# mcu.net
KiCad netlist of a schematic drawn in Altium Designer
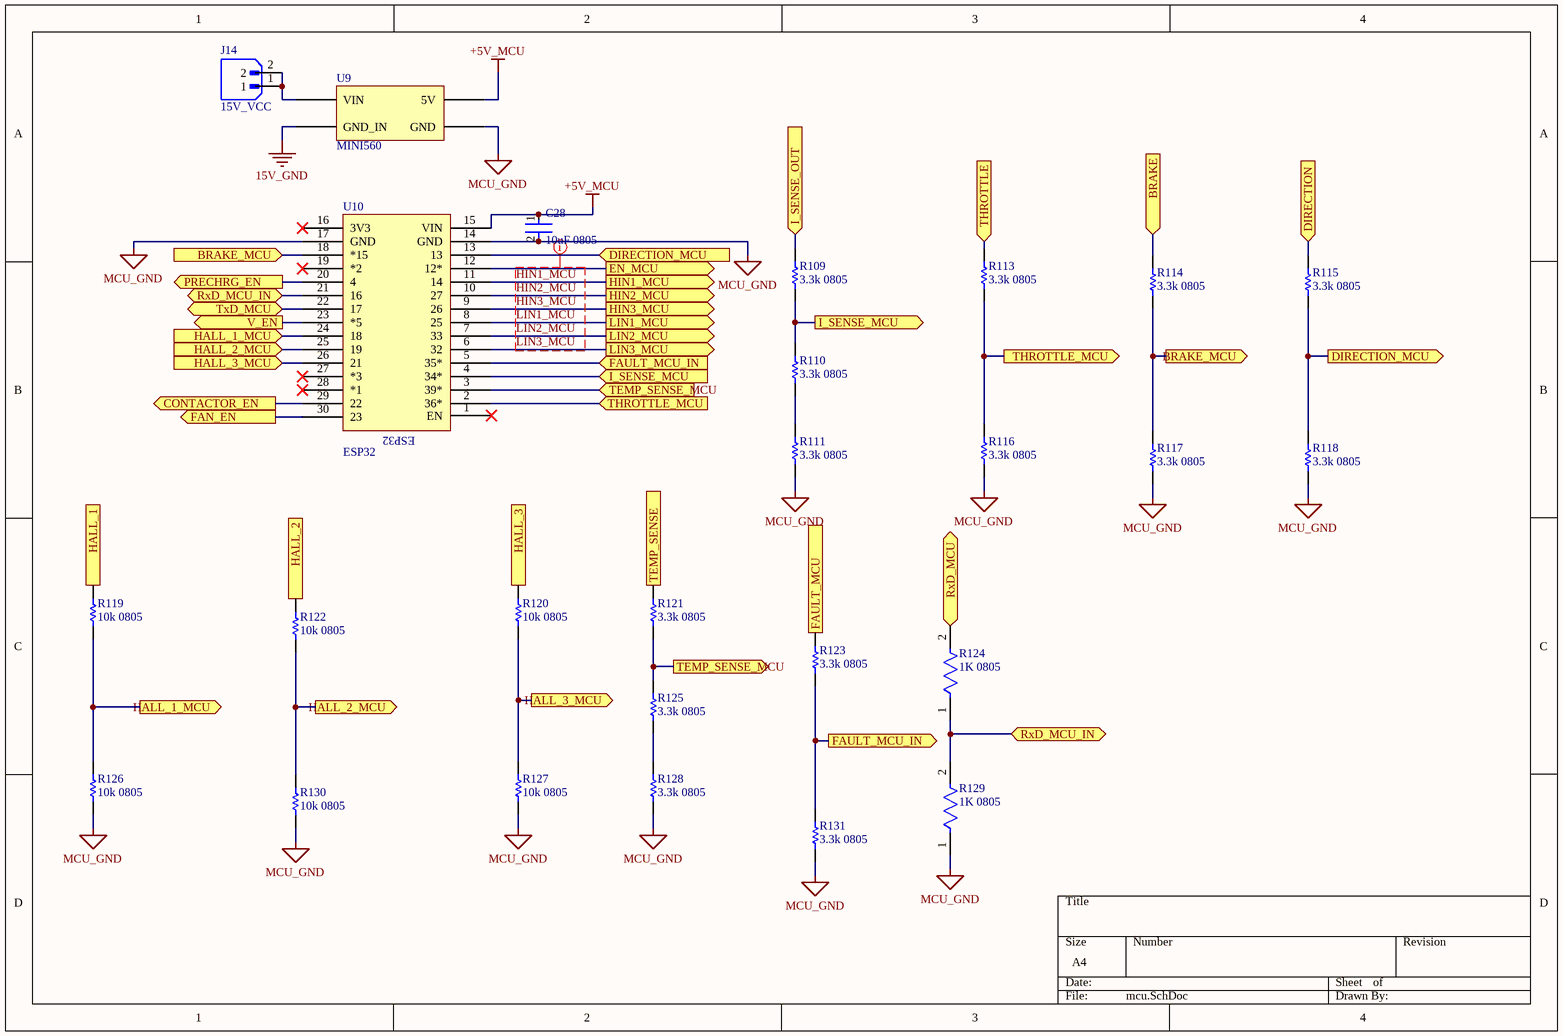
[diagram p0: mcu.SchDoc]

(export (version "E")
  (design (tool "Eeschema 10.0.6"))
  (components
    (comp (ref "C28")
      (value "10uF 0805")
      (footprint "R0805")
      (description "10uF/1000nF 50V Capacitor ±10% Tolerance CC0805KKX5R9BB106 – 0805 Package")
      (libsource (lib "1kW_BLDC_Controller") (part "10uF 0805"))
    )
    (comp (ref "J14")
      (value "15V_VCC")
      (footprint "XH2.5-2p")
      (description "2 Pin JST-XH Male Straight 2515 Connector 2.54mm Pitch")
      (libsource (lib "1kW_BLDC_Controller_1") (part "XH2.5-2p"))
    )
    (comp (ref "R109")
      (value "3.3k 0805")
      (footprint "R0805")
      (description "3.3K Ohm 1/8 Watt Resistor 1% Tolerance RC0805FR-073K3L – 0805 Package")
      (libsource (lib "1kW_BLDC_Controller") (part "R0805"))
    )
    (comp (ref "R110")
      (value "3.3k 0805")
      (footprint "R0805")
      (description "3.3K Ohm 1/8 Watt Resistor 1% Tolerance RC0805FR-073K3L – 0805 Package")
      (libsource (lib "1kW_BLDC_Controller") (part "R0805"))
    )
    (comp (ref "R111")
      (value "3.3k 0805")
      (footprint "R0805")
      (description "3.3K Ohm 1/8 Watt Resistor 1% Tolerance RC0805FR-073K3L – 0805 Package")
      (libsource (lib "1kW_BLDC_Controller") (part "R0805"))
    )
    (comp (ref "R113")
      (value "3.3k 0805")
      (footprint "R0805")
      (description "3.3K Ohm 1/8 Watt Resistor 1% Tolerance RC0805FR-073K3L – 0805 Package")
      (libsource (lib "1kW_BLDC_Controller") (part "R0805"))
    )
    (comp (ref "R114")
      (value "3.3k 0805")
      (footprint "R0805")
      (description "3.3K Ohm 1/8 Watt Resistor 1% Tolerance RC0805FR-073K3L – 0805 Package")
      (libsource (lib "1kW_BLDC_Controller") (part "R0805"))
    )
    (comp (ref "R115")
      (value "3.3k 0805")
      (footprint "R0805")
      (description "3.3K Ohm 1/8 Watt Resistor 1% Tolerance RC0805FR-073K3L – 0805 Package")
      (libsource (lib "1kW_BLDC_Controller") (part "R0805"))
    )
    (comp (ref "R116")
      (value "3.3k 0805")
      (footprint "R0805")
      (description "3.3K Ohm 1/8 Watt Resistor 1% Tolerance RC0805FR-073K3L – 0805 Package")
      (libsource (lib "1kW_BLDC_Controller") (part "R0805"))
    )
    (comp (ref "R117")
      (value "3.3k 0805")
      (footprint "R0805")
      (description "3.3K Ohm 1/8 Watt Resistor 1% Tolerance RC0805FR-073K3L – 0805 Package")
      (libsource (lib "1kW_BLDC_Controller") (part "R0805"))
    )
    (comp (ref "R118")
      (value "3.3k 0805")
      (footprint "R0805")
      (description "3.3K Ohm 1/8 Watt Resistor 1% Tolerance RC0805FR-073K3L – 0805 Package")
      (libsource (lib "1kW_BLDC_Controller") (part "R0805"))
    )
    (comp (ref "R119")
      (value "10k 0805")
      (footprint "R0805")
      (description "10K Ohm 1/8 Watt Resistor 1% Tolerance RC0805FR-0710KL – 0805 Package")
      (libsource (lib "1kW_BLDC_Controller") (part "10k 0805"))
    )
    (comp (ref "R120")
      (value "10k 0805")
      (footprint "R0805")
      (description "10K Ohm 1/8 Watt Resistor 1% Tolerance RC0805FR-0710KL – 0805 Package")
      (libsource (lib "1kW_BLDC_Controller") (part "10k 0805"))
    )
    (comp (ref "R121")
      (value "3.3k 0805")
      (footprint "R0805")
      (description "3.3K Ohm 1/8 Watt Resistor 1% Tolerance RC0805FR-073K3L – 0805 Package")
      (libsource (lib "1kW_BLDC_Controller") (part "R0805"))
    )
    (comp (ref "R122")
      (value "10k 0805")
      (footprint "R0805")
      (description "10K Ohm 1/8 Watt Resistor 1% Tolerance RC0805FR-0710KL – 0805 Package")
      (libsource (lib "1kW_BLDC_Controller") (part "10k 0805"))
    )
    (comp (ref "R123")
      (value "3.3k 0805")
      (footprint "R0805")
      (description "3.3K Ohm 1/8 Watt Resistor 1% Tolerance RC0805FR-073K3L – 0805 Package")
      (libsource (lib "1kW_BLDC_Controller") (part "R0805"))
    )
    (comp (ref "R124")
      (value "1K 0805")
      (footprint "R0805")
      (description "1K Ohm 1/8 Watt Resistor 1% Tolerance 0805S8F1001T5E – 0805 Package")
      (libsource (lib "1kW_BLDC_Controller") (part "1k 0805"))
    )
    (comp (ref "R125")
      (value "3.3k 0805")
      (footprint "R0805")
      (description "3.3K Ohm 1/8 Watt Resistor 1% Tolerance RC0805FR-073K3L – 0805 Package")
      (libsource (lib "1kW_BLDC_Controller") (part "R0805"))
    )
    (comp (ref "R126")
      (value "10k 0805")
      (footprint "R0805")
      (description "10K Ohm 1/8 Watt Resistor 1% Tolerance RC0805FR-0710KL – 0805 Package")
      (libsource (lib "1kW_BLDC_Controller") (part "10k 0805"))
    )
    (comp (ref "R127")
      (value "10k 0805")
      (footprint "R0805")
      (description "10K Ohm 1/8 Watt Resistor 1% Tolerance RC0805FR-0710KL – 0805 Package")
      (libsource (lib "1kW_BLDC_Controller") (part "10k 0805"))
    )
    (comp (ref "R128")
      (value "3.3k 0805")
      (footprint "R0805")
      (description "3.3K Ohm 1/8 Watt Resistor 1% Tolerance RC0805FR-073K3L – 0805 Package")
      (libsource (lib "1kW_BLDC_Controller") (part "R0805"))
    )
    (comp (ref "R129")
      (value "1K 0805")
      (footprint "R0805")
      (description "1K Ohm 1/8 Watt Resistor 1% Tolerance 0805S8F1001T5E – 0805 Package")
      (libsource (lib "1kW_BLDC_Controller") (part "1k 0805"))
    )
    (comp (ref "R130")
      (value "10k 0805")
      (footprint "R0805")
      (description "10K Ohm 1/8 Watt Resistor 1% Tolerance RC0805FR-0710KL – 0805 Package")
      (libsource (lib "1kW_BLDC_Controller") (part "10k 0805"))
    )
    (comp (ref "R131")
      (value "3.3k 0805")
      (footprint "R0805")
      (description "3.3K Ohm 1/8 Watt Resistor 1% Tolerance RC0805FR-073K3L – 0805 Package")
      (libsource (lib "1kW_BLDC_Controller") (part "R0805"))
    )
    (comp (ref "U9")
      (value "MINI560")
      (footprint "MINI560")
      (description "MINI560 5VDC 5A Step-Down Stabilized Module")
      (libsource (lib "1kW_BLDC_Controller") (part "MINI560"))
    )
    (comp (ref "U10")
      (value "ESP32")
      (footprint "esp32")
      (libsource (lib "1kW_BLDC_Controller") (part "ESP32"))
    )
  )
  (nets
    (net (code "1") (name "+5V_MCU") (class "Default")
      (node (ref "C28") (pin "1") (pinfunction "1_1") (pintype "passive"))
      (node (ref "U10") (pin "15") (pinfunction "VIN_15") (pintype "passive"))
      (node (ref "U9") (pin "3") (pinfunction "5V_3") (pintype "power_in"))
    )
    (net (code "2") (name "/BRAKE") (class "Default")
      (node (ref "R114") (pin "2") (pinfunction "2_2") (pintype "passive"))
    )
    (net (code "3") (name "/BRAKE_MCU") (class "Default")
      (node (ref "R114") (pin "1") (pinfunction "1_1") (pintype "passive"))
      (node (ref "R117") (pin "2") (pinfunction "2_2") (pintype "passive"))
      (node (ref "U10") (pin "18") (pinfunction "*15_18") (pintype "passive"))
    )
    (net (code "4") (name "/CONTACTOR_EN") (class "Default")
      (node (ref "U10") (pin "29") (pinfunction "22_29") (pintype "passive"))
    )
    (net (code "5") (name "/DIRECTION") (class "Default")
      (node (ref "R115") (pin "2") (pinfunction "2_2") (pintype "passive"))
    )
    (net (code "6") (name "/DIRECTION_MCU") (class "Default")
      (node (ref "R115") (pin "1") (pinfunction "1_1") (pintype "passive"))
      (node (ref "R118") (pin "2") (pinfunction "2_2") (pintype "passive"))
      (node (ref "U10") (pin "13") (pinfunction "13_13") (pintype "passive"))
    )
    (net (code "7") (name "/EN_MCU") (class "Default")
      (node (ref "U10") (pin "12") (pinfunction "12*_12") (pintype "passive"))
    )
    (net (code "8") (name "/FAN_EN") (class "Default")
      (node (ref "U10") (pin "30") (pinfunction "23_30") (pintype "passive"))
    )
    (net (code "9") (name "/FAULT_MCU") (class "Default")
      (node (ref "R123") (pin "2") (pinfunction "2_2") (pintype "passive"))
    )
    (net (code "10") (name "/FAULT_MCU_IN") (class "Default")
      (node (ref "R123") (pin "1") (pinfunction "1_1") (pintype "passive"))
      (node (ref "R131") (pin "2") (pinfunction "2_2") (pintype "passive"))
      (node (ref "U10") (pin "5") (pinfunction "35*_5") (pintype "passive"))
    )
    (net (code "11") (name "/HALL_1") (class "Default")
      (node (ref "R119") (pin "2") (pinfunction "2_2") (pintype "passive"))
    )
    (net (code "12") (name "/HALL_1_MCU") (class "Default")
      (node (ref "R119") (pin "1") (pinfunction "1_1") (pintype "passive"))
      (node (ref "R126") (pin "2") (pinfunction "2_2") (pintype "passive"))
      (node (ref "U10") (pin "24") (pinfunction "18_24") (pintype "passive"))
    )
    (net (code "13") (name "/HALL_2") (class "Default")
      (node (ref "R122") (pin "2") (pinfunction "2_2") (pintype "passive"))
    )
    (net (code "14") (name "/HALL_2_MCU") (class "Default")
      (node (ref "R122") (pin "1") (pinfunction "1_1") (pintype "passive"))
      (node (ref "R130") (pin "2") (pinfunction "2_2") (pintype "passive"))
      (node (ref "U10") (pin "25") (pinfunction "19_25") (pintype "passive"))
    )
    (net (code "15") (name "/HALL_3") (class "Default")
      (node (ref "R120") (pin "2") (pinfunction "2_2") (pintype "passive"))
    )
    (net (code "16") (name "/HALL_3_MCU") (class "Default")
      (node (ref "R120") (pin "1") (pinfunction "1_1") (pintype "passive"))
      (node (ref "R127") (pin "2") (pinfunction "2_2") (pintype "passive"))
      (node (ref "U10") (pin "26") (pinfunction "21_26") (pintype "passive"))
    )
    (net (code "17") (name "/HIN1_MCU") (class "Default")
      (node (ref "U10") (pin "11") (pinfunction "14_11") (pintype "passive"))
    )
    (net (code "18") (name "/HIN2_MCU") (class "Default")
      (node (ref "U10") (pin "10") (pinfunction "27_10") (pintype "passive"))
    )
    (net (code "19") (name "/HIN3_MCU") (class "Default")
      (node (ref "U10") (pin "9") (pinfunction "26_9") (pintype "passive"))
    )
    (net (code "20") (name "/I_SENSE_MCU") (class "Default")
      (node (ref "R109") (pin "1") (pinfunction "1_1") (pintype "passive"))
      (node (ref "R110") (pin "2") (pinfunction "2_2") (pintype "passive"))
      (node (ref "U10") (pin "4") (pinfunction "34*_4") (pintype "passive"))
    )
    (net (code "21") (name "/I_SENSE_OUT") (class "Default")
      (node (ref "R109") (pin "2") (pinfunction "2_2") (pintype "passive"))
    )
    (net (code "22") (name "/LIN1_MCU") (class "Default")
      (node (ref "U10") (pin "8") (pinfunction "25_8") (pintype "passive"))
    )
    (net (code "23") (name "/LIN2_MCU") (class "Default")
      (node (ref "U10") (pin "7") (pinfunction "33_7") (pintype "passive"))
    )
    (net (code "24") (name "/LIN3_MCU") (class "Default")
      (node (ref "U10") (pin "6") (pinfunction "32_6") (pintype "passive"))
    )
    (net (code "25") (name "/PRECHRG_EN") (class "Default")
      (node (ref "U10") (pin "20") (pinfunction "4_20") (pintype "passive"))
    )
    (net (code "26") (name "/RxD_MCU") (class "Default")
      (node (ref "R124") (pin "2") (pinfunction "2_2") (pintype "passive"))
    )
    (net (code "27") (name "/RxD_MCU_IN") (class "Default")
      (node (ref "R124") (pin "1") (pinfunction "1_1") (pintype "passive"))
      (node (ref "R129") (pin "2") (pinfunction "2_2") (pintype "passive"))
      (node (ref "U10") (pin "21") (pinfunction "16_21") (pintype "passive"))
    )
    (net (code "28") (name "/TEMP_SENSE") (class "Default")
      (node (ref "R121") (pin "2") (pinfunction "2_2") (pintype "passive"))
    )
    (net (code "29") (name "/TEMP_SENSE_MCU") (class "Default")
      (node (ref "R121") (pin "1") (pinfunction "1_1") (pintype "passive"))
      (node (ref "R125") (pin "2") (pinfunction "2_2") (pintype "passive"))
      (node (ref "U10") (pin "3") (pinfunction "39*_3") (pintype "passive"))
    )
    (net (code "30") (name "/THROTTLE") (class "Default")
      (node (ref "R113") (pin "2") (pinfunction "2_2") (pintype "passive"))
    )
    (net (code "31") (name "/THROTTLE_MCU") (class "Default")
      (node (ref "R113") (pin "1") (pinfunction "1_1") (pintype "passive"))
      (node (ref "R116") (pin "2") (pinfunction "2_2") (pintype "passive"))
      (node (ref "U10") (pin "2") (pinfunction "36*_2") (pintype "passive"))
    )
    (net (code "32") (name "/TxD_MCU") (class "Default")
      (node (ref "U10") (pin "22") (pinfunction "17_22") (pintype "passive"))
    )
    (net (code "33") (name "/V_EN") (class "Default")
      (node (ref "U10") (pin "23") (pinfunction "*5_23") (pintype "passive"))
    )
    (net (code "34") (name "15V_GND") (class "Default")
      (node (ref "U9") (pin "2") (pinfunction "GND_IN_2") (pintype "power_in"))
    )
    (net (code "35") (name "MCU_GND") (class "Default")
      (node (ref "C28") (pin "2") (pinfunction "2_2") (pintype "passive"))
      (node (ref "R111") (pin "1") (pinfunction "1_1") (pintype "passive"))
      (node (ref "R116") (pin "1") (pinfunction "1_1") (pintype "passive"))
      (node (ref "R117") (pin "1") (pinfunction "1_1") (pintype "passive"))
      (node (ref "R118") (pin "1") (pinfunction "1_1") (pintype "passive"))
      (node (ref "R126") (pin "1") (pinfunction "1_1") (pintype "passive"))
      (node (ref "R127") (pin "1") (pinfunction "1_1") (pintype "passive"))
      (node (ref "R128") (pin "1") (pinfunction "1_1") (pintype "passive"))
      (node (ref "R129") (pin "1") (pinfunction "1_1") (pintype "passive"))
      (node (ref "R130") (pin "1") (pinfunction "1_1") (pintype "passive"))
      (node (ref "R131") (pin "1") (pinfunction "1_1") (pintype "passive"))
      (node (ref "U10") (pin "14") (pinfunction "GND_14") (pintype "passive"))
      (node (ref "U10") (pin "17") (pinfunction "GND_17") (pintype "passive"))
      (node (ref "U9") (pin "4") (pinfunction "GND_4") (pintype "power_in"))
    )
    (net (code "36") (name "Net-(R110-Pad1)") (class "Default")
      (node (ref "R110") (pin "1") (pinfunction "1_1") (pintype "passive"))
      (node (ref "R111") (pin "2") (pinfunction "2_2") (pintype "passive"))
    )
    (net (code "37") (name "Net-(R125-Pad1)") (class "Default")
      (node (ref "R125") (pin "1") (pinfunction "1_1") (pintype "passive"))
      (node (ref "R128") (pin "2") (pinfunction "2_2") (pintype "passive"))
    )
    (net (code "38") (name "Net-(U9-VIN)") (class "Default")
      (node (ref "J14") (pin "1") (pinfunction "1_1") (pintype "passive"))
      (node (ref "J14") (pin "2") (pinfunction "2_2") (pintype "passive"))
      (node (ref "U9") (pin "1") (pinfunction "VIN_1") (pintype "power_in"))
    )
    (net (code "39") (name "unconnected-(U10-*1-Pad28)") (class "Default")
      (node (ref "U10") (pin "28") (pinfunction "*1_28") (pintype "passive+no_connect"))
    )
    (net (code "40") (name "unconnected-(U10-*2-Pad19)") (class "Default")
      (node (ref "U10") (pin "19") (pinfunction "*2_19") (pintype "passive+no_connect"))
    )
    (net (code "41") (name "unconnected-(U10-*3-Pad27)") (class "Default")
      (node (ref "U10") (pin "27") (pinfunction "*3_27") (pintype "passive+no_connect"))
    )
    (net (code "42") (name "unconnected-(U10-3V3-Pad16)") (class "Default")
      (node (ref "U10") (pin "16") (pinfunction "3V3_16") (pintype "passive+no_connect"))
    )
    (net (code "43") (name "unconnected-(U10-EN-Pad1)") (class "Default")
      (node (ref "U10") (pin "1") (pinfunction "EN_1") (pintype "passive+no_connect"))
    )
  )
)
